# photodiode_board.net
KiCad netlist of a schematic drawn in EAGLE
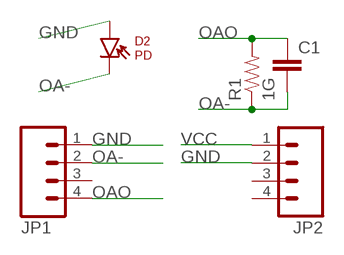
[diagram p0: schematic, sheet 1]

(export (version "E")
  (design (tool "Eeschema 10.0.6"))
  (components
    (comp (ref "C1")
      (value "CAPTH_0.1-CAP")
      (footprint "eagle-import:TH_0.1-CAP")
      (libsource (lib "eagle-import") (part "CAPTH_0.1-CAP"))
    )
    (comp (ref "D2")
      (value "PD")
      (footprint "eagle-import:TH_0.1-PD")
      (libsource (lib "eagle-import") (part "PD"))
    )
    (comp (ref "JP1")
      (value "M04PTH")
      (footprint "eagle-import:1X04")
      (libsource (lib "eagle-import") (part "M04PTH"))
    )
    (comp (ref "JP2")
      (value "M04PTH")
      (footprint "eagle-import:1X04")
      (libsource (lib "eagle-import") (part "M04PTH"))
    )
    (comp (ref "R1")
      (value "1G")
      (footprint "eagle-import:TH_0.3-RES")
      (libsource (lib "eagle-import") (part "RESISTORAXIAL-0.3"))
    )
  )
  (nets
    (net (code "1") (name "/GND") (class "Default")
      (node (ref "D2") (pin "A") (pinfunction "A_A") (pintype "bidirectional"))
      (node (ref "JP1") (pin "1") (pinfunction "1_1") (pintype "passive"))
      (node (ref "JP2") (pin "2") (pinfunction "2_2") (pintype "passive"))
    )
    (net (code "2") (name "/OA-") (class "Default")
      (node (ref "C1") (pin "2") (pinfunction "2_2") (pintype "passive"))
      (node (ref "D2") (pin "C") (pinfunction "C_C") (pintype "bidirectional"))
      (node (ref "JP1") (pin "2") (pinfunction "2_2") (pintype "passive"))
      (node (ref "R1") (pin "P$1") (pinfunction "1_P$1") (pintype "passive"))
    )
    (net (code "3") (name "/OAO") (class "Default")
      (node (ref "C1") (pin "1") (pinfunction "1_1") (pintype "passive"))
      (node (ref "JP1") (pin "4") (pinfunction "4_4") (pintype "passive"))
      (node (ref "R1") (pin "P$2") (pinfunction "2_P$2") (pintype "passive"))
    )
    (net (code "4") (name "/VCC") (class "Default")
      (node (ref "JP2") (pin "1") (pinfunction "1_1") (pintype "passive"))
    )
    (net (code "5") (name "unconnected-(JP1-Pad3)") (class "Default")
      (node (ref "JP1") (pin "3") (pinfunction "3_3") (pintype "passive"))
    )
    (net (code "6") (name "unconnected-(JP2-Pad3)") (class "Default")
      (node (ref "JP2") (pin "3") (pinfunction "3_3") (pintype "passive"))
    )
    (net (code "7") (name "unconnected-(JP2-Pad4)") (class "Default")
      (node (ref "JP2") (pin "4") (pinfunction "4_4") (pintype "passive"))
    )
  )
)
